# breakoutbrd.net
KiCad netlist of a schematic drawn in EAGLE
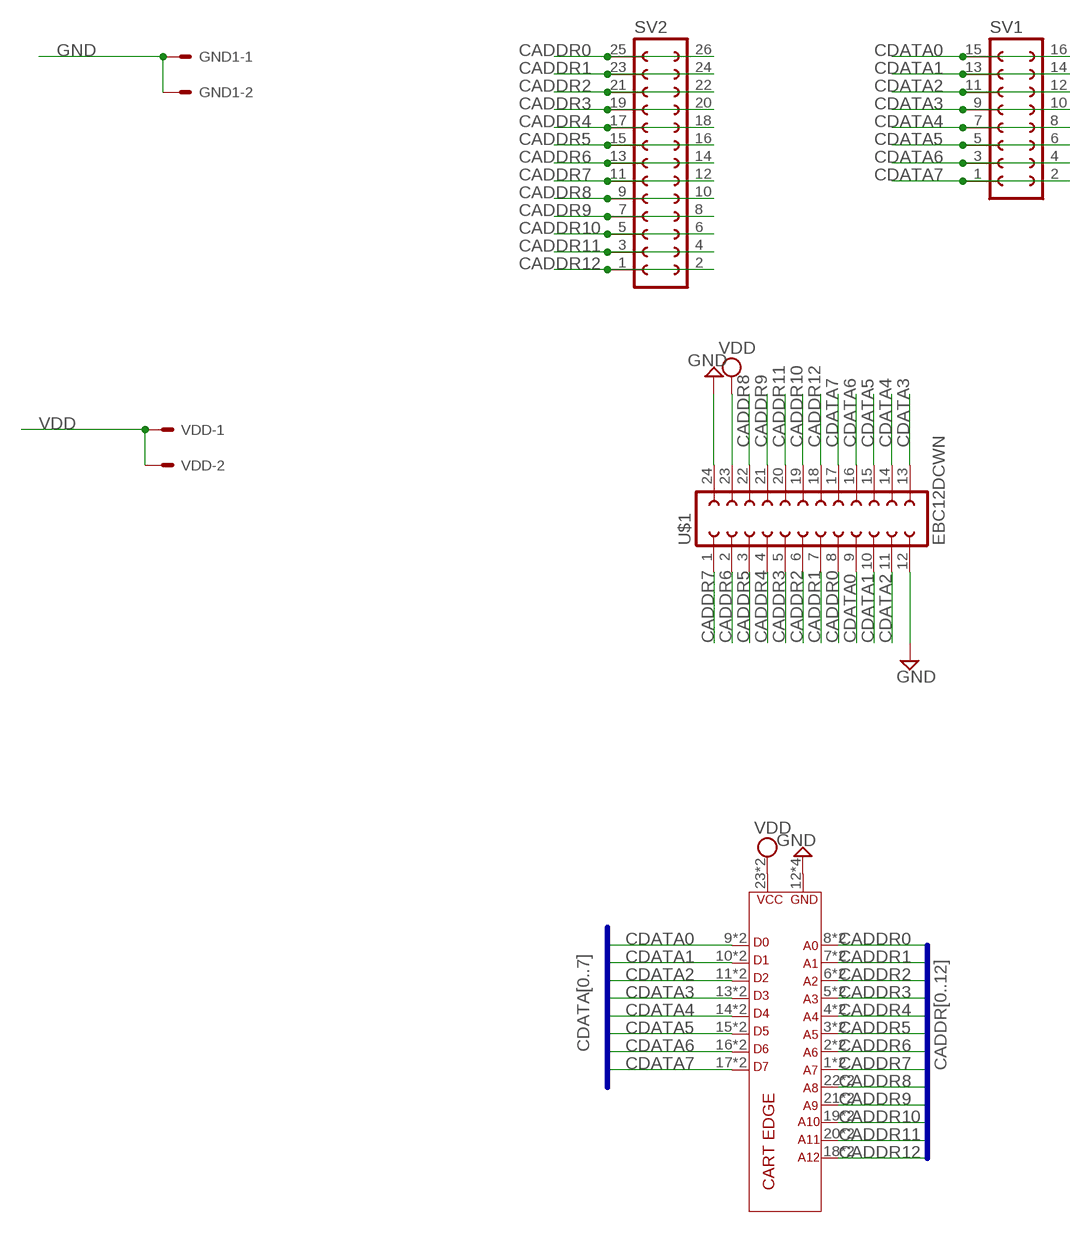
[diagram p0: schematic, sheet 1]

(export (version "E")
  (design (tool "Eeschema 10.0.6"))
  (components
    (comp (ref "GND1")
      (value "22-23-2021")
      (footprint "eagle-import:22-23-2021")
      (fields (field (name "MF") "MOLEX"))
      (libsource (lib "eagle-import") (part "22-23-2021"))
    )
    (comp (ref "J1")
      (value "ATARI-2600")
      (footprint "eagle-import:BREAKOUT_BOARD")
      (libsource (lib "eagle-import") (part "ATARI-2600"))
    )
    (comp (ref "SV1")
      (value "FE08-2")
      (footprint "eagle-import:FE08-2")
      (libsource (lib "eagle-import") (part "FE08-2"))
    )
    (comp (ref "SV2")
      (value "FE13-2")
      (footprint "eagle-import:FE13-2")
      (libsource (lib "eagle-import") (part "FE13-2"))
    )
    (comp (ref "U$1")
      (value "EBC12DCWN")
      (footprint "eagle-import:EBC12DCWN")
      (libsource (lib "eagle-import") (part "EBC12DCWN"))
    )
    (comp (ref "VDD")
      (value "22-23-2021")
      (footprint "eagle-import:22-23-2021")
      (fields (field (name "MF") "MOLEX"))
      (libsource (lib "eagle-import") (part "22-23-2021"))
    )
  )
  (nets
    (net (code "1") (name "/CADDR0") (class "Default")
      (node (ref "J1") (pin "32") (pinfunction "A0_32") (pintype "bidirectional"))
      (node (ref "J1") (pin "8") (pinfunction "A0_8") (pintype "bidirectional"))
      (node (ref "SV2") (pin "25") (pinfunction "25_25") (pintype "passive"))
      (node (ref "SV2") (pin "26") (pinfunction "26_26") (pintype "passive"))
      (node (ref "U$1") (pin "8") (pinfunction "8_8") (pintype "passive"))
    )
    (net (code "2") (name "/CADDR1") (class "Default")
      (node (ref "J1") (pin "31") (pinfunction "A1_31") (pintype "bidirectional"))
      (node (ref "J1") (pin "7") (pinfunction "A1_7") (pintype "bidirectional"))
      (node (ref "SV2") (pin "23") (pinfunction "23_23") (pintype "passive"))
      (node (ref "SV2") (pin "24") (pinfunction "24_24") (pintype "passive"))
      (node (ref "U$1") (pin "7") (pinfunction "7_7") (pintype "passive"))
    )
    (net (code "3") (name "/CADDR2") (class "Default")
      (node (ref "J1") (pin "30") (pinfunction "A2_30") (pintype "bidirectional"))
      (node (ref "J1") (pin "6") (pinfunction "A2_6") (pintype "bidirectional"))
      (node (ref "SV2") (pin "21") (pinfunction "21_21") (pintype "passive"))
      (node (ref "SV2") (pin "22") (pinfunction "22_22") (pintype "passive"))
      (node (ref "U$1") (pin "6") (pinfunction "6_6") (pintype "passive"))
    )
    (net (code "4") (name "/CADDR3") (class "Default")
      (node (ref "J1") (pin "29") (pinfunction "A3_29") (pintype "bidirectional"))
      (node (ref "J1") (pin "5") (pinfunction "A3_5") (pintype "bidirectional"))
      (node (ref "SV2") (pin "19") (pinfunction "19_19") (pintype "passive"))
      (node (ref "SV2") (pin "20") (pinfunction "20_20") (pintype "passive"))
      (node (ref "U$1") (pin "5") (pinfunction "5_5") (pintype "passive"))
    )
    (net (code "5") (name "/CADDR4") (class "Default")
      (node (ref "J1") (pin "28") (pinfunction "A4_28") (pintype "bidirectional"))
      (node (ref "J1") (pin "4") (pinfunction "A4_4") (pintype "bidirectional"))
      (node (ref "SV2") (pin "17") (pinfunction "17_17") (pintype "passive"))
      (node (ref "SV2") (pin "18") (pinfunction "18_18") (pintype "passive"))
      (node (ref "U$1") (pin "4") (pinfunction "4_4") (pintype "passive"))
    )
    (net (code "6") (name "/CADDR5") (class "Default")
      (node (ref "J1") (pin "27") (pinfunction "A5_27") (pintype "bidirectional"))
      (node (ref "J1") (pin "3") (pinfunction "A5_3") (pintype "bidirectional"))
      (node (ref "SV2") (pin "15") (pinfunction "15_15") (pintype "passive"))
      (node (ref "SV2") (pin "16") (pinfunction "16_16") (pintype "passive"))
      (node (ref "U$1") (pin "3") (pinfunction "3_3") (pintype "passive"))
    )
    (net (code "7") (name "/CADDR6") (class "Default")
      (node (ref "J1") (pin "2") (pinfunction "A6_2") (pintype "bidirectional"))
      (node (ref "J1") (pin "26") (pinfunction "A6_26") (pintype "bidirectional"))
      (node (ref "SV2") (pin "13") (pinfunction "13_13") (pintype "passive"))
      (node (ref "SV2") (pin "14") (pinfunction "14_14") (pintype "passive"))
      (node (ref "U$1") (pin "2") (pinfunction "2_2") (pintype "passive"))
    )
    (net (code "8") (name "/CADDR7") (class "Default")
      (node (ref "J1") (pin "1") (pinfunction "A7_1") (pintype "bidirectional"))
      (node (ref "J1") (pin "25") (pinfunction "A7_25") (pintype "bidirectional"))
      (node (ref "SV2") (pin "11") (pinfunction "11_11") (pintype "passive"))
      (node (ref "SV2") (pin "12") (pinfunction "12_12") (pintype "passive"))
      (node (ref "U$1") (pin "1") (pinfunction "1_1") (pintype "passive"))
    )
    (net (code "9") (name "/CADDR8") (class "Default")
      (node (ref "J1") (pin "22") (pinfunction "A8_22") (pintype "bidirectional"))
      (node (ref "J1") (pin "46") (pinfunction "A8_46") (pintype "bidirectional"))
      (node (ref "SV2") (pin "10") (pinfunction "10_10") (pintype "passive"))
      (node (ref "SV2") (pin "9") (pinfunction "9_9") (pintype "passive"))
      (node (ref "U$1") (pin "22") (pinfunction "22_22") (pintype "passive"))
    )
    (net (code "10") (name "/CADDR9") (class "Default")
      (node (ref "J1") (pin "21") (pinfunction "A9_21") (pintype "bidirectional"))
      (node (ref "J1") (pin "45") (pinfunction "A9_45") (pintype "bidirectional"))
      (node (ref "SV2") (pin "7") (pinfunction "7_7") (pintype "passive"))
      (node (ref "SV2") (pin "8") (pinfunction "8_8") (pintype "passive"))
      (node (ref "U$1") (pin "21") (pinfunction "21_21") (pintype "passive"))
    )
    (net (code "11") (name "/CADDR10") (class "Default")
      (node (ref "J1") (pin "19") (pinfunction "A10_19") (pintype "bidirectional"))
      (node (ref "J1") (pin "43") (pinfunction "A10_43") (pintype "bidirectional"))
      (node (ref "SV2") (pin "5") (pinfunction "5_5") (pintype "passive"))
      (node (ref "SV2") (pin "6") (pinfunction "6_6") (pintype "passive"))
      (node (ref "U$1") (pin "19") (pinfunction "19_19") (pintype "passive"))
    )
    (net (code "12") (name "/CADDR11") (class "Default")
      (node (ref "J1") (pin "20") (pinfunction "A11_20") (pintype "bidirectional"))
      (node (ref "J1") (pin "44") (pinfunction "A11_44") (pintype "bidirectional"))
      (node (ref "SV2") (pin "3") (pinfunction "3_3") (pintype "passive"))
      (node (ref "SV2") (pin "4") (pinfunction "4_4") (pintype "passive"))
      (node (ref "U$1") (pin "20") (pinfunction "20_20") (pintype "passive"))
    )
    (net (code "13") (name "/CADDR12") (class "Default")
      (node (ref "J1") (pin "18") (pinfunction "A12_18") (pintype "bidirectional"))
      (node (ref "J1") (pin "42") (pinfunction "A12_42") (pintype "bidirectional"))
      (node (ref "SV2") (pin "1") (pinfunction "1_1") (pintype "passive"))
      (node (ref "SV2") (pin "2") (pinfunction "2_2") (pintype "passive"))
      (node (ref "U$1") (pin "18") (pinfunction "18_18") (pintype "passive"))
    )
    (net (code "15") (name "/CDATA0") (class "Default")
      (node (ref "J1") (pin "33") (pinfunction "D0_33") (pintype "bidirectional"))
      (node (ref "J1") (pin "9") (pinfunction "D0_9") (pintype "bidirectional"))
      (node (ref "SV1") (pin "15") (pinfunction "15_15") (pintype "passive"))
      (node (ref "SV1") (pin "16") (pinfunction "16_16") (pintype "passive"))
      (node (ref "U$1") (pin "9") (pinfunction "9_9") (pintype "passive"))
    )
    (net (code "16") (name "/CDATA1") (class "Default")
      (node (ref "J1") (pin "10") (pinfunction "D1_10") (pintype "bidirectional"))
      (node (ref "J1") (pin "34") (pinfunction "D1_34") (pintype "bidirectional"))
      (node (ref "SV1") (pin "13") (pinfunction "13_13") (pintype "passive"))
      (node (ref "SV1") (pin "14") (pinfunction "14_14") (pintype "passive"))
      (node (ref "U$1") (pin "10") (pinfunction "10_10") (pintype "passive"))
    )
    (net (code "17") (name "/CDATA2") (class "Default")
      (node (ref "J1") (pin "11") (pinfunction "D2_11") (pintype "bidirectional"))
      (node (ref "J1") (pin "35") (pinfunction "D2_35") (pintype "bidirectional"))
      (node (ref "SV1") (pin "11") (pinfunction "11_11") (pintype "passive"))
      (node (ref "SV1") (pin "12") (pinfunction "12_12") (pintype "passive"))
      (node (ref "U$1") (pin "11") (pinfunction "11_11") (pintype "passive"))
    )
    (net (code "18") (name "/CDATA3") (class "Default")
      (node (ref "J1") (pin "13") (pinfunction "D3_13") (pintype "bidirectional"))
      (node (ref "J1") (pin "37") (pinfunction "D3_37") (pintype "bidirectional"))
      (node (ref "SV1") (pin "10") (pinfunction "10_10") (pintype "passive"))
      (node (ref "SV1") (pin "9") (pinfunction "9_9") (pintype "passive"))
      (node (ref "U$1") (pin "13") (pinfunction "13_13") (pintype "passive"))
    )
    (net (code "19") (name "/CDATA4") (class "Default")
      (node (ref "J1") (pin "14") (pinfunction "D4_14") (pintype "bidirectional"))
      (node (ref "J1") (pin "38") (pinfunction "D4_38") (pintype "bidirectional"))
      (node (ref "SV1") (pin "7") (pinfunction "7_7") (pintype "passive"))
      (node (ref "SV1") (pin "8") (pinfunction "8_8") (pintype "passive"))
      (node (ref "U$1") (pin "14") (pinfunction "14_14") (pintype "passive"))
    )
    (net (code "20") (name "/CDATA5") (class "Default")
      (node (ref "J1") (pin "15") (pinfunction "D5_15") (pintype "bidirectional"))
      (node (ref "J1") (pin "39") (pinfunction "D5_39") (pintype "bidirectional"))
      (node (ref "SV1") (pin "5") (pinfunction "5_5") (pintype "passive"))
      (node (ref "SV1") (pin "6") (pinfunction "6_6") (pintype "passive"))
      (node (ref "U$1") (pin "15") (pinfunction "15_15") (pintype "passive"))
    )
    (net (code "21") (name "/CDATA6") (class "Default")
      (node (ref "J1") (pin "16") (pinfunction "D6_16") (pintype "bidirectional"))
      (node (ref "J1") (pin "40") (pinfunction "D6_40") (pintype "bidirectional"))
      (node (ref "SV1") (pin "3") (pinfunction "3_3") (pintype "passive"))
      (node (ref "SV1") (pin "4") (pinfunction "4_4") (pintype "passive"))
      (node (ref "U$1") (pin "16") (pinfunction "16_16") (pintype "passive"))
    )
    (net (code "22") (name "/CDATA7") (class "Default")
      (node (ref "J1") (pin "17") (pinfunction "D7_17") (pintype "bidirectional"))
      (node (ref "J1") (pin "41") (pinfunction "D7_41") (pintype "bidirectional"))
      (node (ref "SV1") (pin "1") (pinfunction "1_1") (pintype "passive"))
      (node (ref "SV1") (pin "2") (pinfunction "2_2") (pintype "passive"))
      (node (ref "U$1") (pin "17") (pinfunction "17_17") (pintype "passive"))
    )
    (net (code "24") (name "GND") (class "Default")
      (node (ref "GND1") (pin "1") (pinfunction "S_1") (pintype "passive"))
      (node (ref "GND1") (pin "2") (pinfunction "S_2") (pintype "passive"))
      (node (ref "J1") (pin "12") (pinfunction "GND_12") (pintype "power_in"))
      (node (ref "J1") (pin "24") (pinfunction "GND_24") (pintype "power_in"))
      (node (ref "J1") (pin "36") (pinfunction "GND_36") (pintype "power_in"))
      (node (ref "J1") (pin "48") (pinfunction "GND_48") (pintype "power_in"))
      (node (ref "U$1") (pin "12") (pinfunction "12_12") (pintype "passive"))
      (node (ref "U$1") (pin "24") (pinfunction "24_24") (pintype "passive"))
    )
    (net (code "25") (name "VDD") (class "Default")
      (node (ref "J1") (pin "23") (pinfunction "VCC_23") (pintype "power_in"))
      (node (ref "J1") (pin "47") (pinfunction "VCC_47") (pintype "power_in"))
      (node (ref "U$1") (pin "23") (pinfunction "23_23") (pintype "passive"))
      (node (ref "VDD") (pin "1") (pinfunction "S_1") (pintype "passive"))
      (node (ref "VDD") (pin "2") (pinfunction "S_2") (pintype "passive"))
    )
  )
)
